# Acuator-MKI-RevisionCD.net
KiCad netlist of a schematic drawn in EAGLE
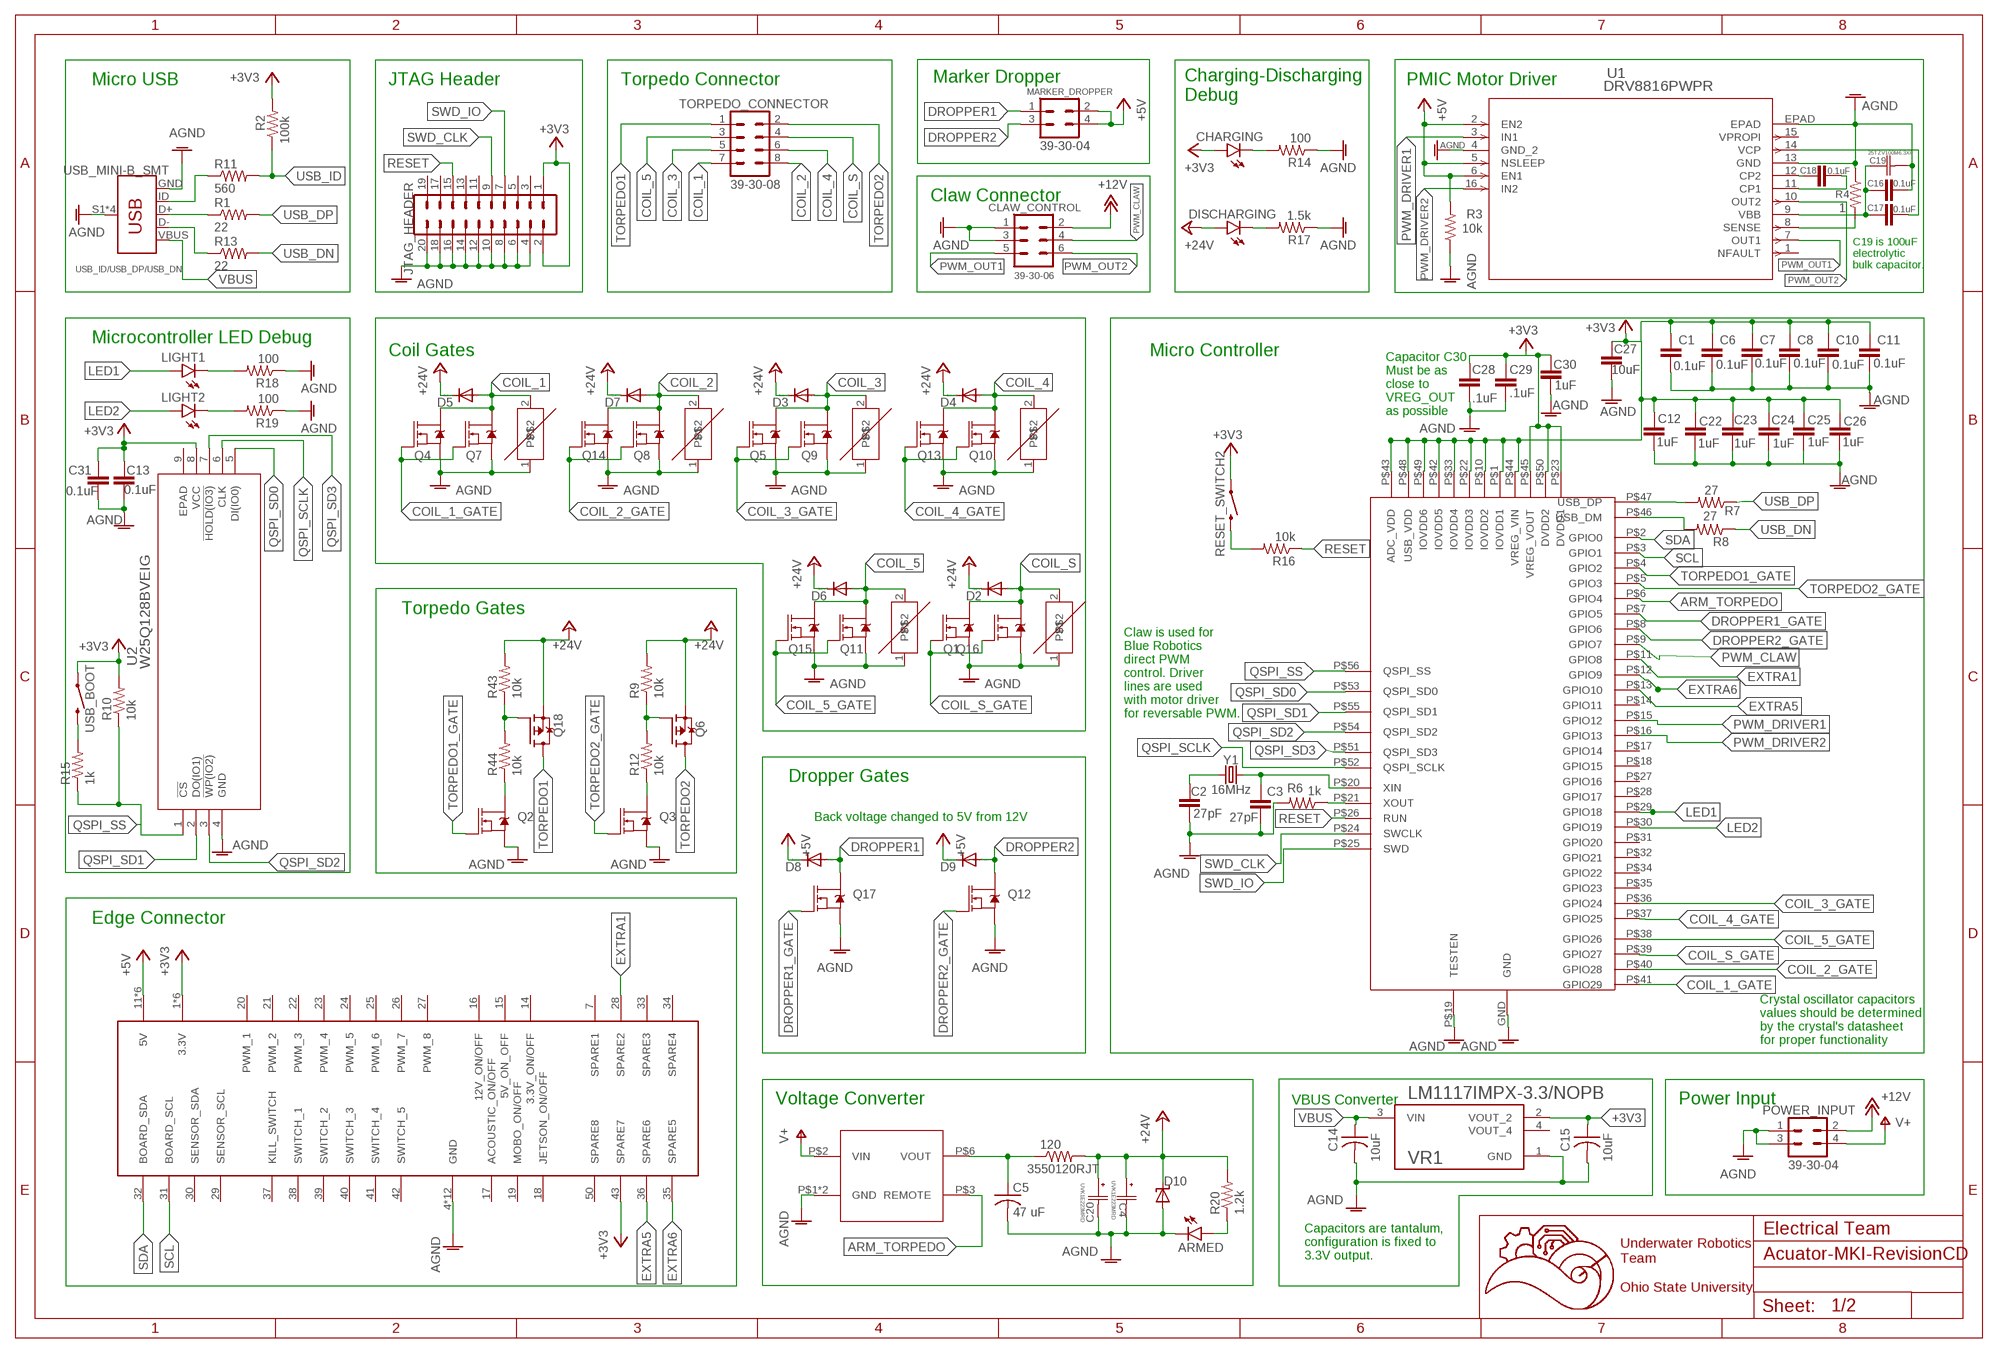
[diagram p0: schematic, sheet 1]
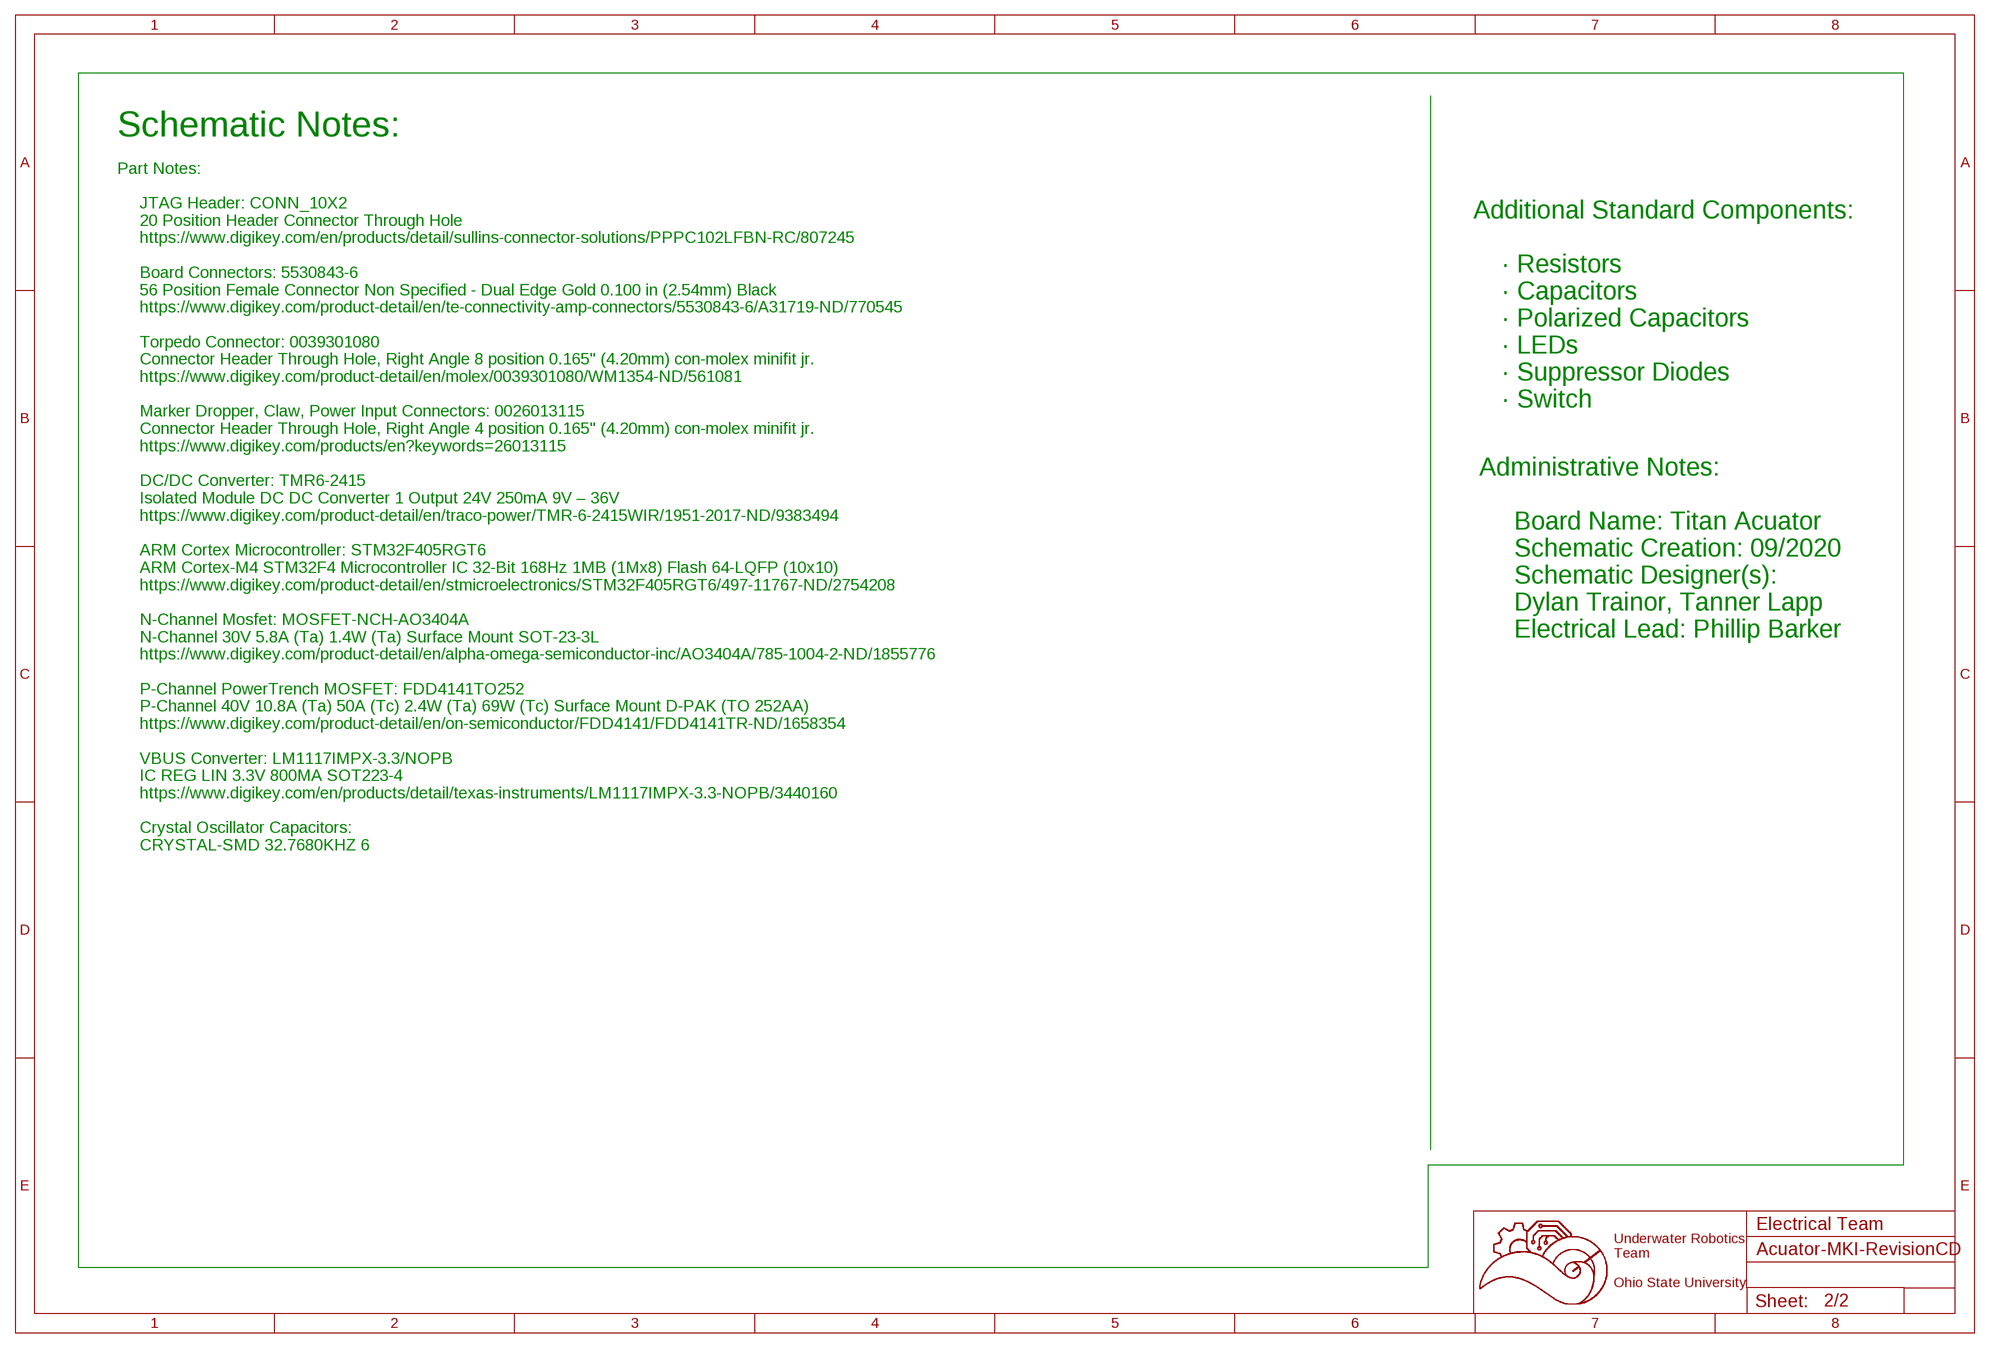
[diagram p1: schematic, sheet 2]

(export (version "E")
  (design (tool "Eeschema 10.0.6"))
  (components
    (comp (ref "120")
      (value "3550120RJT")
      (footprint "eagle-import:3550120RJT")
      (libsource (lib "eagle-import") (part "3550120RJT"))
    )
    (comp (ref "ARMED")
      (value "LEDCHIPLED_0603")
      (footprint "eagle-import:CHIPLED_0603")
      (libsource (lib "eagle-import") (part "LEDCHIPLED_0603"))
    )
    (comp (ref "C1")
      (value "0.1uF")
      (footprint "eagle-import:C0603")
      (libsource (lib "eagle-import") (part "C-EUC0603"))
    )
    (comp (ref "C2")
      (value "27pF")
      (footprint "eagle-import:C0603")
      (libsource (lib "eagle-import") (part "C-EUC0603"))
    )
    (comp (ref "C3")
      (value "27pF")
      (footprint "eagle-import:C0603")
      (libsource (lib "eagle-import") (part "C-EUC0603"))
    )
    (comp (ref "C4")
      (value "UVK1E223MRD")
      (footprint "eagle-import:CAP_UFW_25X50_NCH")
      (fields (field (name "COPYRIGHT") "Copyright (C) 2018 Accelerated Designs. All rights reserved"))
      (libsource (lib "eagle-import") (part "UVK1E223MRD"))
    )
    (comp (ref "C5")
      (value "47 uF")
      (footprint "eagle-import:C1206K")
      (libsource (lib "eagle-import") (part "resistor_348_C-USC1206K"))
    )
    (comp (ref "C6")
      (value "0.1uF")
      (footprint "eagle-import:C0603")
      (libsource (lib "eagle-import") (part "C-EUC0603"))
    )
    (comp (ref "C7")
      (value "0.1uF")
      (footprint "eagle-import:C0603")
      (libsource (lib "eagle-import") (part "C-EUC0603"))
    )
    (comp (ref "C8")
      (value "0.1uF")
      (footprint "eagle-import:C0603")
      (libsource (lib "eagle-import") (part "C-EUC0603"))
    )
    (comp (ref "C10")
      (value "0.1uF")
      (footprint "eagle-import:C0603")
      (libsource (lib "eagle-import") (part "C-EUC0603"))
    )
    (comp (ref "C11")
      (value "0.1uF")
      (footprint "eagle-import:C0603")
      (libsource (lib "eagle-import") (part "C-EUC0603"))
    )
    (comp (ref "C12")
      (value "1uF")
      (footprint "eagle-import:C0603")
      (libsource (lib "eagle-import") (part "C-EUC0603"))
    )
    (comp (ref "C13")
      (value "0.1uF")
      (footprint "eagle-import:C0603")
      (libsource (lib "eagle-import") (part "C-EUC0603"))
    )
    (comp (ref "C14")
      (value "10uF")
      (footprint "eagle-import:C0603")
      (libsource (lib "eagle-import") (part "C-USC0603"))
    )
    (comp (ref "C15")
      (value "10uF")
      (footprint "eagle-import:C0603")
      (libsource (lib "eagle-import") (part "C-USC0603"))
    )
    (comp (ref "C16")
      (value "0.1uF")
      (footprint "eagle-import:C0603")
      (libsource (lib "eagle-import") (part "C-EUC0603"))
    )
    (comp (ref "C17")
      (value "0.1uF")
      (footprint "eagle-import:C0603")
      (libsource (lib "eagle-import") (part "C-EUC0603"))
    )
    (comp (ref "C18")
      (value "0.1uF")
      (footprint "eagle-import:C0603")
      (libsource (lib "eagle-import") (part "C-EUC0603"))
    )
    (comp (ref "C19")
      (value "25TZV100M6.3X8")
      (footprint "eagle-import:CAP_J-V_6P3X8_RUB")
      (fields (field (name "COPYRIGHT") "Copyright (C) 2018 Accelerated Designs. All rights reserved"))
      (libsource (lib "eagle-import") (part "25TZV100M6.3X8"))
    )
    (comp (ref "C20")
      (value "UVK1E223MRD")
      (footprint "eagle-import:CAP_UFW_25X50_NCH")
      (fields (field (name "COPYRIGHT") "Copyright (C) 2018 Accelerated Designs. All rights reserved"))
      (libsource (lib "eagle-import") (part "UVK1E223MRD"))
    )
    (comp (ref "C22")
      (value "1uF")
      (footprint "eagle-import:C0603")
      (libsource (lib "eagle-import") (part "C-EUC0603"))
    )
    (comp (ref "C23")
      (value "1uF")
      (footprint "eagle-import:C0603")
      (libsource (lib "eagle-import") (part "C-EUC0603"))
    )
    (comp (ref "C24")
      (value "1uF")
      (footprint "eagle-import:C0603")
      (libsource (lib "eagle-import") (part "C-EUC0603"))
    )
    (comp (ref "C25")
      (value "1uF")
      (footprint "eagle-import:C0603")
      (libsource (lib "eagle-import") (part "C-EUC0603"))
    )
    (comp (ref "C26")
      (value "1uF")
      (footprint "eagle-import:C0603")
      (libsource (lib "eagle-import") (part "C-EUC0603"))
    )
    (comp (ref "C27")
      (value "10uF")
      (footprint "eagle-import:C0603")
      (libsource (lib "eagle-import") (part "C-EUC0603"))
    )
    (comp (ref "C28")
      (value ".1uF")
      (footprint "eagle-import:C0603")
      (libsource (lib "eagle-import") (part "C-EUC0603"))
    )
    (comp (ref "C29")
      (value ".1uF")
      (footprint "eagle-import:C0603")
      (libsource (lib "eagle-import") (part "C-EUC0603"))
    )
    (comp (ref "C30")
      (value "1uF")
      (footprint "eagle-import:C0603")
      (libsource (lib "eagle-import") (part "C-EUC0603"))
    )
    (comp (ref "C31")
      (value "0.1uF")
      (footprint "eagle-import:C0603")
      (libsource (lib "eagle-import") (part "C-EUC0603"))
    )
    (comp (ref "CHARGING")
      (value "LEDCHIPLED_0603")
      (footprint "eagle-import:CHIPLED_0603")
      (libsource (lib "eagle-import") (part "LEDCHIPLED_0603"))
    )
    (comp (ref "CLAW_CONTROL")
      (value "39-30-06")
      (footprint "eagle-import:39-30-_06_")
      (libsource (lib "eagle-import") (part "39-30-?06?"))
    )
    (comp (ref "D2")
      (value "DIODE-SMB")
      (footprint "eagle-import:SMB")
      (libsource (lib "eagle-import") (part "DIODE-SMB"))
    )
    (comp (ref "D3")
      (value "DIODE-SMB")
      (footprint "eagle-import:SMB")
      (libsource (lib "eagle-import") (part "DIODE-SMB"))
    )
    (comp (ref "D4")
      (value "DIODE-SMB")
      (footprint "eagle-import:SMB")
      (libsource (lib "eagle-import") (part "DIODE-SMB"))
    )
    (comp (ref "D5")
      (value "DIODE-SMB")
      (footprint "eagle-import:SMB")
      (libsource (lib "eagle-import") (part "DIODE-SMB"))
    )
    (comp (ref "D6")
      (value "DIODE-SMB")
      (footprint "eagle-import:SMB")
      (libsource (lib "eagle-import") (part "DIODE-SMB"))
    )
    (comp (ref "D7")
      (value "DIODE-SMB")
      (footprint "eagle-import:SMB")
      (libsource (lib "eagle-import") (part "DIODE-SMB"))
    )
    (comp (ref "D8")
      (value "DIODE-SMB")
      (footprint "eagle-import:SMB")
      (libsource (lib "eagle-import") (part "DIODE-SMB"))
    )
    (comp (ref "D9")
      (value "DIODE-SMB")
      (footprint "eagle-import:SMB")
      (libsource (lib "eagle-import") (part "DIODE-SMB"))
    )
    (comp (ref "D10")
      (value "SUPPRESSOR-SMBJ")
      (footprint "eagle-import:SMBJ")
      (libsource (lib "eagle-import") (part "SUPPRESSOR-SMBJ"))
    )
    (comp (ref "DISCHARGING")
      (value "LEDCHIPLED_0603")
      (footprint "eagle-import:CHIPLED_0603")
      (libsource (lib "eagle-import") (part "LEDCHIPLED_0603"))
    )
    (comp (ref "JTAG_HEADER")
      (value "CONN_10X2")
      (footprint "eagle-import:2X10")
      (libsource (lib "eagle-import") (part "CONN_10X2"))
    )
    (comp (ref "LIGHT1")
      (value "LEDCHIPLED_0603")
      (footprint "eagle-import:CHIPLED_0603")
      (libsource (lib "eagle-import") (part "LEDCHIPLED_0603"))
    )
    (comp (ref "LIGHT2")
      (value "LEDCHIPLED_0603")
      (footprint "eagle-import:CHIPLED_0603")
      (libsource (lib "eagle-import") (part "LEDCHIPLED_0603"))
    )
    (comp (ref "MARKER_DROPPER")
      (value "39-30-04")
      (footprint "eagle-import:39-30-_04_")
      (libsource (lib "eagle-import") (part "39-30-?04?"))
    )
    (comp (ref "POWER_INPUT")
      (value "39-30-04")
      (footprint "eagle-import:39-30-_04_")
      (libsource (lib "eagle-import") (part "39-30-?04?"))
    )
    (comp (ref "Q1")
      (value "MOSFET-NCH-AO3404A")
      (footprint "eagle-import:SOT23-3")
      (libsource (lib "eagle-import") (part "MOSFET-NCH-AO3404A"))
    )
    (comp (ref "Q2")
      (value "MOSFET-NCH-AO3404A")
      (footprint "eagle-import:SOT23-3")
      (libsource (lib "eagle-import") (part "MOSFET-NCH-AO3404A"))
    )
    (comp (ref "Q3")
      (value "MOSFET-NCH-AO3404A")
      (footprint "eagle-import:SOT23-3")
      (libsource (lib "eagle-import") (part "MOSFET-NCH-AO3404A"))
    )
    (comp (ref "Q4")
      (value "MOSFET-NCH-AO3404A")
      (footprint "eagle-import:SOT23-3")
      (libsource (lib "eagle-import") (part "MOSFET-NCH-AO3404A"))
    )
    (comp (ref "Q5")
      (value "MOSFET-NCH-AO3404A")
      (footprint "eagle-import:SOT23-3")
      (libsource (lib "eagle-import") (part "MOSFET-NCH-AO3404A"))
    )
    (comp (ref "Q6")
      (value "FDD4141TO252")
      (footprint "eagle-import:TO252")
      (libsource (lib "eagle-import") (part "FDD4141TO252"))
    )
    (comp (ref "Q7")
      (value "MOSFET-NCH-AO3404A")
      (footprint "eagle-import:SOT23-3")
      (libsource (lib "eagle-import") (part "MOSFET-NCH-AO3404A"))
    )
    (comp (ref "Q8")
      (value "MOSFET-NCH-AO3404A")
      (footprint "eagle-import:SOT23-3")
      (libsource (lib "eagle-import") (part "MOSFET-NCH-AO3404A"))
    )
    (comp (ref "Q9")
      (value "MOSFET-NCH-AO3404A")
      (footprint "eagle-import:SOT23-3")
      (libsource (lib "eagle-import") (part "MOSFET-NCH-AO3404A"))
    )
    (comp (ref "Q10")
      (value "MOSFET-NCH-AO3404A")
      (footprint "eagle-import:SOT23-3")
      (libsource (lib "eagle-import") (part "MOSFET-NCH-AO3404A"))
    )
    (comp (ref "Q11")
      (value "MOSFET-NCH-AO3404A")
      (footprint "eagle-import:SOT23-3")
      (libsource (lib "eagle-import") (part "MOSFET-NCH-AO3404A"))
    )
    (comp (ref "Q12")
      (value "MOSFET-NCH-AO3404A")
      (footprint "eagle-import:SOT23-3")
      (libsource (lib "eagle-import") (part "MOSFET-NCH-AO3404A"))
    )
    (comp (ref "Q13")
      (value "MOSFET-NCH-AO3404A")
      (footprint "eagle-import:SOT23-3")
      (libsource (lib "eagle-import") (part "MOSFET-NCH-AO3404A"))
    )
    (comp (ref "Q14")
      (value "MOSFET-NCH-AO3404A")
      (footprint "eagle-import:SOT23-3")
      (libsource (lib "eagle-import") (part "MOSFET-NCH-AO3404A"))
    )
    (comp (ref "Q15")
      (value "MOSFET-NCH-AO3404A")
      (footprint "eagle-import:SOT23-3")
      (libsource (lib "eagle-import") (part "MOSFET-NCH-AO3404A"))
    )
    (comp (ref "Q16")
      (value "MOSFET-NCH-AO3404A")
      (footprint "eagle-import:SOT23-3")
      (libsource (lib "eagle-import") (part "MOSFET-NCH-AO3404A"))
    )
    (comp (ref "Q17")
      (value "MOSFET-NCH-AO3404A")
      (footprint "eagle-import:SOT23-3")
      (libsource (lib "eagle-import") (part "MOSFET-NCH-AO3404A"))
    )
    (comp (ref "Q18")
      (value "FDD4141TO252")
      (footprint "eagle-import:TO252")
      (libsource (lib "eagle-import") (part "FDD4141TO252"))
    )
    (comp (ref "R1")
      (value "22")
      (footprint "eagle-import:R0603")
      (libsource (lib "eagle-import") (part "R-US_R0603"))
    )
    (comp (ref "R2")
      (value "100k")
      (footprint "eagle-import:R0603")
      (libsource (lib "eagle-import") (part "R-US_R0603"))
    )
    (comp (ref "R3")
      (value "10k")
      (footprint "eagle-import:R0603")
      (libsource (lib "eagle-import") (part "resistor_348_R-US_R0603"))
    )
    (comp (ref "R4")
      (value "1")
      (footprint "eagle-import:R0805")
      (libsource (lib "eagle-import") (part "resistor_348_R-US_R0805"))
    )
    (comp (ref "R6")
      (value "1k")
      (footprint "eagle-import:R0603")
      (libsource (lib "eagle-import") (part "R-US_R0603"))
    )
    (comp (ref "R7")
      (value "27")
      (footprint "eagle-import:R0603")
      (libsource (lib "eagle-import") (part "R-US_R0603"))
    )
    (comp (ref "R8")
      (value "27")
      (footprint "eagle-import:R0603")
      (libsource (lib "eagle-import") (part "R-US_R0603"))
    )
    (comp (ref "R9")
      (value "10k")
      (footprint "eagle-import:R0603")
      (libsource (lib "eagle-import") (part "resistor_348_R-US_R0603"))
    )
    (comp (ref "R10")
      (value "10k")
      (footprint "eagle-import:R0603")
      (libsource (lib "eagle-import") (part "R-US_R0603"))
    )
    (comp (ref "R11")
      (value "560")
      (footprint "eagle-import:R0603")
      (libsource (lib "eagle-import") (part "R-US_R0603"))
    )
    (comp (ref "R12")
      (value "10k")
      (footprint "eagle-import:R0603")
      (libsource (lib "eagle-import") (part "resistor_348_R-US_R0603"))
    )
    (comp (ref "R13")
      (value "22")
      (footprint "eagle-import:R0603")
      (libsource (lib "eagle-import") (part "R-US_R0603"))
    )
    (comp (ref "R14")
      (value "100")
      (footprint "eagle-import:R0805")
      (libsource (lib "eagle-import") (part "resistor_348_R-US_R0805"))
    )
    (comp (ref "R15")
      (value "1k")
      (footprint "eagle-import:R0603")
      (libsource (lib "eagle-import") (part "R-US_R0603"))
    )
    (comp (ref "R16")
      (value "10k")
      (footprint "eagle-import:R0603")
      (libsource (lib "eagle-import") (part "R-US_R0603"))
    )
    (comp (ref "R17")
      (value "1.5k")
      (footprint "eagle-import:R0805")
      (libsource (lib "eagle-import") (part "resistor_348_R-US_R0805"))
    )
    (comp (ref "R18")
      (value "100")
      (footprint "eagle-import:R0805")
      (libsource (lib "eagle-import") (part "resistor_348_R-US_R0805"))
    )
    (comp (ref "R19")
      (value "100")
      (footprint "eagle-import:R0805")
      (libsource (lib "eagle-import") (part "resistor_348_R-US_R0805"))
    )
    (comp (ref "R20")
      (value "1.2k")
      (footprint "eagle-import:R0805")
      (libsource (lib "eagle-import") (part "resistor_348_R-US_R0805"))
    )
    (comp (ref "R43")
      (value "10k")
      (footprint "eagle-import:R0603")
      (libsource (lib "eagle-import") (part "resistor_348_R-US_R0603"))
    )
    (comp (ref "R44")
      (value "10k")
      (footprint "eagle-import:R0603")
      (libsource (lib "eagle-import") (part "resistor_348_R-US_R0603"))
    )
    (comp (ref "RESET_SWITCH2")
      (value "MOMENTARY-SWITCH-SPST-PTH-6.0MM")
      (footprint "eagle-import:TACTILE_SWITCH_PTH_6.0MM")
      (libsource (lib "eagle-import") (part "MOMENTARY-SWITCH-SPST-PTH-6.0MM"))
    )
    (comp (ref "TORPEDO_CONNECTOR")
      (value "39-30-08")
      (footprint "eagle-import:39-30-_08_")
      (libsource (lib "eagle-import") (part "39-30-?08?"))
    )
    (comp (ref "U$1")
      (value "5530843-EDGE")
      (footprint "eagle-import:5530843-6-BOARDFINGERS")
      (libsource (lib "eagle-import") (part "5530843-EDGE"))
    )
    (comp (ref "U$2")
      (value "ERZ-VF2M270ERZ-VF2M270")
      (footprint "eagle-import:RESM8060X320N")
      (libsource (lib "eagle-import") (part "ERZ-VF2M270ERZ-VF2M270"))
    )
    (comp (ref "U$3")
      (value "ERZ-VF2M270ERZ-VF2M270")
      (footprint "eagle-import:RESM8060X320N")
      (libsource (lib "eagle-import") (part "ERZ-VF2M270ERZ-VF2M270"))
    )
    (comp (ref "U$4")
      (value "ERZ-VF2M270ERZ-VF2M270")
      (footprint "eagle-import:RESM8060X320N")
      (libsource (lib "eagle-import") (part "ERZ-VF2M270ERZ-VF2M270"))
    )
    (comp (ref "U$5")
      (value "ERZ-VF2M270ERZ-VF2M270")
      (footprint "eagle-import:RESM8060X320N")
      (libsource (lib "eagle-import") (part "ERZ-VF2M270ERZ-VF2M270"))
    )
    (comp (ref "U$6")
      (value "TMR6-2415")
      (footprint "eagle-import:TMR6-2415")
      (libsource (lib "eagle-import") (part "TMR6-2415"))
    )
    (comp (ref "U$7")
      (value "ERZ-VF2M270ERZ-VF2M270")
      (footprint "eagle-import:RESM8060X320N")
      (libsource (lib "eagle-import") (part "ERZ-VF2M270ERZ-VF2M270"))
    )
    (comp (ref "U$8")
      (value "ERZ-VF2M270ERZ-VF2M270")
      (footprint "eagle-import:RESM8060X320N")
      (libsource (lib "eagle-import") (part "ERZ-VF2M270ERZ-VF2M270"))
    )
    (comp (ref "U$9")
      (value "RP2040")
      (footprint "eagle-import:RP2040")
      (libsource (lib "eagle-import") (part "RP2040"))
    )
    (comp (ref "U1")
      (value "DRV8816PWPR")
      (footprint "eagle-import:PWP_16")
      (libsource (lib "eagle-import") (part "DRV8816PWPR"))
    )
    (comp (ref "U2")
      (value "W25Q128BVEIG")
      (footprint "eagle-import:WIN_E-8_WIN")
      (fields (field (name "COPYRIGHT") "Copyright (C) 2021 Ultra Librarian. All rights reserved."))
      (libsource (lib "eagle-import") (part "W25Q128BVEIG"))
    )
    (comp (ref "USB_BOOT")
      (value "MOMENTARY-SWITCH-SPST-PTH-6.0MM")
      (footprint "eagle-import:TACTILE_SWITCH_PTH_6.0MM")
      (libsource (lib "eagle-import") (part "MOMENTARY-SWITCH-SPST-PTH-6.0MM"))
    )
    (comp (ref "USB_ID/USB_DP/USB_DN")
      (value "USB_MINI-B_SMT")
      (footprint "eagle-import:USB-MINIB")
      (libsource (lib "eagle-import") (part "USB_MINI-B_SMT"))
    )
    (comp (ref "VR1")
      (value "LM1117IMPX-3.3/NOPB")
      (footprint "eagle-import:VREG_LM1117IMPX-3.3_NOPB")
      (fields (field (name "MF") "Texas Instruments"))
      (libsource (lib "eagle-import") (part "LM1117IMPX-3.3/NOPB"))
    )
    (comp (ref "Y1")
      (value "16MHz")
      (footprint "eagle-import:HC49US")
      (libsource (lib "eagle-import") (part "CRYSTAL-16MHZPTH-HC49US"))
    )
  )
  (nets
    (net (code "1") (name "+3V3") (class "Default")
      (node (ref "C1") (pin "1") (pinfunction "1_1") (pintype "passive"))
      (node (ref "C10") (pin "1") (pinfunction "1_1") (pintype "passive"))
      (node (ref "C11") (pin "1") (pinfunction "1_1") (pintype "passive"))
      (node (ref "C12") (pin "1") (pinfunction "1_1") (pintype "passive"))
      (node (ref "C13") (pin "1") (pinfunction "1_1") (pintype "passive"))
      (node (ref "C15") (pin "1") (pinfunction "1_1") (pintype "passive"))
      (node (ref "C22") (pin "1") (pinfunction "1_1") (pintype "passive"))
      (node (ref "C23") (pin "1") (pinfunction "1_1") (pintype "passive"))
      (node (ref "C24") (pin "1") (pinfunction "1_1") (pintype "passive"))
      (node (ref "C25") (pin "1") (pinfunction "1_1") (pintype "passive"))
      (node (ref "C26") (pin "1") (pinfunction "1_1") (pintype "passive"))
      (node (ref "C27") (pin "1") (pinfunction "1_1") (pintype "passive"))
      (node (ref "C28") (pin "1") (pinfunction "1_1") (pintype "passive"))
      (node (ref "C29") (pin "1") (pinfunction "1_1") (pintype "passive"))
      (node (ref "C30") (pin "1") (pinfunction "1_1") (pintype "passive"))
      (node (ref "C31") (pin "1") (pinfunction "1_1") (pintype "passive"))
      (node (ref "C6") (pin "1") (pinfunction "1_1") (pintype "passive"))
      (node (ref "C7") (pin "1") (pinfunction "1_1") (pintype "passive"))
      (node (ref "C8") (pin "1") (pinfunction "1_1") (pintype "passive"))
      (node (ref "CHARGING") (pin "A") (pinfunction "A_A") (pintype "passive"))
      (node (ref "JTAG_HEADER") (pin "1") (pinfunction "1_1") (pintype "passive"))
      (node (ref "JTAG_HEADER") (pin "2") (pinfunction "2_2") (pintype "passive"))
      (node (ref "R10") (pin "2") (pinfunction "2_2") (pintype "passive"))
      (node (ref "R2") (pin "2") (pinfunction "2_2") (pintype "passive"))
      (node (ref "RESET_SWITCH2") (pin "1") (pinfunction "1_1") (pintype "passive"))
      (node (ref "U$1") (pin "1") (pinfunction "3.3V_1") (pintype "bidirectional"))
      (node (ref "U$1") (pin "2") (pinfunction "3.3V_2") (pintype "bidirectional"))
      (node (ref "U$1") (pin "3") (pinfunction "3.3V_3") (pintype "bidirectional"))
      (node (ref "U$1") (pin "43") (pinfunction "SPARE7_43") (pintype "bidirectional"))
      (node (ref "U$1") (pin "54") (pinfunction "3.3V_54") (pintype "bidirectional"))
      (node (ref "U$1") (pin "55") (pinfunction "3.3V_55") (pintype "bidirectional"))
      (node (ref "U$1") (pin "56") (pinfunction "3.3V_56") (pintype "bidirectional"))
      (node (ref "U$9") (pin "P$1") (pinfunction "IOVDD1_P$1") (pintype "bidirectional"))
      (node (ref "U$9") (pin "P$10") (pinfunction "IOVDD2_P$10") (pintype "bidirectional"))
      (node (ref "U$9") (pin "P$22") (pinfunction "IOVDD3_P$22") (pintype "bidirectional"))
      (node (ref "U$9") (pin "P$23") (pinfunction "DVDD1_P$23") (pintype "bidirectional"))
      (node (ref "U$9") (pin "P$33") (pinfunction "IOVDD4_P$33") (pintype "bidirectional"))
      (node (ref "U$9") (pin "P$42") (pinfunction "IOVDD5_P$42") (pintype "bidirectional"))
      (node (ref "U$9") (pin "P$43") (pinfunction "ADC_VDD_P$43") (pintype "bidirectional"))
      (node (ref "U$9") (pin "P$44") (pinfunction "VREG_VIN_P$44") (pintype "bidirectional"))
      (node (ref "U$9") (pin "P$45") (pinfunction "VREG_VOUT_P$45") (pintype "bidirectional"))
      (node (ref "U$9") (pin "P$48") (pinfunction "USB_VDD_P$48") (pintype "bidirectional"))
      (node (ref "U$9") (pin "P$49") (pinfunction "IOVDD6_P$49") (pintype "bidirectional"))
      (node (ref "U$9") (pin "P$50") (pinfunction "DVDD2_P$50") (pintype "bidirectional"))
      (node (ref "U2") (pin "8") (pinfunction "VCC_8") (pintype "power_in"))
      (node (ref "USB_BOOT") (pin "1") (pinfunction "1_1") (pintype "passive"))
      (node (ref "VR1") (pin "2") (pinfunction "VOUT_2_2") (pintype "output"))
    )
    (net (code "2") (name "+5V") (class "Default")
      (node (ref "D8") (pin "C") (pinfunction "C_C") (pintype "passive"))
      (node (ref "D9") (pin "C") (pinfunction "C_C") (pintype "passive"))
      (node (ref "MARKER_DROPPER") (pin "2") (pinfunction "2_2") (pintype "passive"))
      (node (ref "MARKER_DROPPER") (pin "4") (pinfunction "4_4") (pintype "passive"))
      (node (ref "R3") (pin "2") (pinfunction "2_2") (pintype "passive"))
      (node (ref "U$1") (pin "11") (pinfunction "5V_11") (pintype "bidirectional"))
      (node (ref "U$1") (pin "12") (pinfunction "5V_12") (pintype "bidirectional"))
      (node (ref "U$1") (pin "13") (pinfunction "5V_13") (pintype "bidirectional"))
      (node (ref "U$1") (pin "44") (pinfunction "5V_44") (pintype "bidirectional"))
      (node (ref "U$1") (pin "45") (pinfunction "5V_45") (pintype "bidirectional"))
      (node (ref "U$1") (pin "46") (pinfunction "5V_46") (pintype "bidirectional"))
      (node (ref "U1") (pin "2") (pinfunction "EN2_2") (pintype "input"))
      (node (ref "U1") (pin "5") (pinfunction "NSLEEP_5") (pintype "input"))
      (node (ref "U1") (pin "6") (pinfunction "EN1_6") (pintype "input"))
    )
    (net (code "3") (name "+12V") (class "Default")
      (node (ref "CLAW_CONTROL") (pin "2") (pinfunction "2_2") (pintype "passive"))
      (node (ref "POWER_INPUT") (pin "2") (pinfunction "2_2") (pintype "passive"))
    )
    (net (code "4") (name "+24V") (class "Default")
      (node (ref "120") (pin "P$2") (pinfunction "2_P$2") (pintype "passive"))
      (node (ref "C20") (pin "1") (pinfunction "1_1") (pintype "passive"))
      (node (ref "C4") (pin "1") (pinfunction "1_1") (pintype "passive"))
      (node (ref "D10") (pin "C") (pinfunction "C_C") (pintype "passive"))
      (node (ref "D2") (pin "C") (pinfunction "C_C") (pintype "passive"))
      (node (ref "D3") (pin "C") (pinfunction "C_C") (pintype "passive"))
      (node (ref "D4") (pin "C") (pinfunction "C_C") (pintype "passive"))
      (node (ref "D5") (pin "C") (pinfunction "C_C") (pintype "passive"))
      (node (ref "D6") (pin "C") (pinfunction "C_C") (pintype "passive"))
      (node (ref "D7") (pin "C") (pinfunction "C_C") (pintype "passive"))
      (node (ref "DISCHARGING") (pin "A") (pinfunction "A_A") (pintype "passive"))
      (node (ref "Q18") (pin "2") (pinfunction "S_2") (pintype "passive"))
      (node (ref "Q6") (pin "2") (pinfunction "S_2") (pintype "passive"))
      (node (ref "R20") (pin "2") (pinfunction "2_2") (pintype "passive"))
      (node (ref "R43") (pin "2") (pinfunction "2_2") (pintype "passive"))
      (node (ref "R9") (pin "2") (pinfunction "2_2") (pintype "passive"))
    )
    (net (code "5") (name "AGND") (class "Default")
      (node (ref "ARMED") (pin "C") (pinfunction "C_C") (pintype "passive"))
      (node (ref "C1") (pin "2") (pinfunction "2_2") (pintype "passive"))
      (node (ref "C10") (pin "2") (pinfunction "2_2") (pintype "passive"))
      (node (ref "C11") (pin "2") (pinfunction "2_2") (pintype "passive"))
      (node (ref "C12") (pin "2") (pinfunction "2_2") (pintype "passive"))
      (node (ref "C13") (pin "2") (pinfunction "2_2") (pintype "passive"))
      (node (ref "C14") (pin "2") (pinfunction "2_2") (pintype "passive"))
      (node (ref "C15") (pin "2") (pinfunction "2_2") (pintype "passive"))
      (node (ref "C16") (pin "2") (pinfunction "2_2") (pintype "passive"))
      (node (ref "C19") (pin "2") (pinfunction "2_2") (pintype "passive"))
      (node (ref "C2") (pin "2") (pinfunction "2_2") (pintype "passive"))
      (node (ref "C20") (pin "2") (pinfunction "2_2") (pintype "passive"))
      (node (ref "C22") (pin "2") (pinfunction "2_2") (pintype "passive"))
      (node (ref "C23") (pin "2") (pinfunction "2_2") (pintype "passive"))
      (node (ref "C24") (pin "2") (pinfunction "2_2") (pintype "passive"))
      (node (ref "C25") (pin "2") (pinfunction "2_2") (pintype "passive"))
      (node (ref "C26") (pin "2") (pinfunction "2_2") (pintype "passive"))
      (node (ref "C27") (pin "2") (pinfunction "2_2") (pintype "passive"))
      (node (ref "C28") (pin "2") (pinfunction "2_2") (pintype "passive"))
      (node (ref "C29") (pin "2") (pinfunction "2_2") (pintype "passive"))
      (node (ref "C3") (pin "2") (pinfunction "2_2") (pintype "passive"))
      (node (ref "C30") (pin "2") (pinfunction "2_2") (pintype "passive"))
      (node (ref "C31") (pin "2") (pinfunction "2_2") (pintype "passive"))
      (node (ref "C4") (pin "2") (pinfunction "2_2") (pintype "passive"))
      (node (ref "C5") (pin "2") (pinfunction "2_2") (pintype "passive"))
      (node (ref "C6") (pin "2") (pinfunction "2_2") (pintype "passive"))
      (node (ref "C7") (pin "2") (pinfunction "2_2") (pintype "passive"))
      (node (ref "C8") (pin "2") (pinfunction "2_2") (pintype "passive"))
      (node (ref "CLAW_CONTROL") (pin "1") (pinfunction "1_1") (pintype "passive"))
      (node (ref "CLAW_CONTROL") (pin "3") (pinfunction "3_3") (pintype "passive"))
      (node (ref "D10") (pin "A") (pinfunction "A_A") (pintype "passive"))
      (node (ref "JTAG_HEADER") (pin "10") (pinfunction "10_10") (pintype "passive"))
      (node (ref "JTAG_HEADER") (pin "12") (pinfunction "12_12") (pintype "passive"))
      (node (ref "JTAG_HEADER") (pin "14") (pinfunction "14_14") (pintype "passive"))
      (node (ref "JTAG_HEADER") (pin "16") (pinfunction "16_16") (pintype "passive"))
      (node (ref "JTAG_HEADER") (pin "18") (pinfunction "18_18") (pintype "passive"))
      (node (ref "JTAG_HEADER") (pin "20") (pinfunction "20_20") (pintype "passive"))
      (node (ref "JTAG_HEADER") (pin "4") (pinfunction "4_4") (pintype "passive"))
      (node (ref "JTAG_HEADER") (pin "6") (pinfunction "6_6") (pintype "passive"))
      (node (ref "JTAG_HEADER") (pin "8") (pinfunction "8_8") (pintype "passive"))
      (node (ref "POWER_INPUT") (pin "1") (pinfunction "1_1") (pintype "passive"))
      (node (ref "POWER_INPUT") (pin "3") (pinfunction "3_3") (pintype "passive"))
      (node (ref "Q1") (pin "2") (pinfunction "S_2") (pintype "bidirectional"))
      (node (ref "Q10") (pin "2") (pinfunction "S_2") (pintype "bidirectional"))
      (node (ref "Q11") (pin "2") (pinfunction "S_2") (pintype "bidirectional"))
      (node (ref "Q12") (pin "2") (pinfunction "S_2") (pintype "bidirectional"))
      (node (ref "Q13") (pin "2") (pinfunction "S_2") (pintype "bidirectional"))
      (node (ref "Q14") (pin "2") (pinfunction "S_2") (pintype "bidirectional"))
      (node (ref "Q15") (pin "2") (pinfunction "S_2") (pintype "bidirectional"))
      (node (ref "Q16") (pin "2") (pinfunction "S_2") (pintype "bidirectional"))
      (node (ref "Q17") (pin "2") (pinfunction "S_2") (pintype "bidirectional"))
      (node (ref "Q2") (pin "2") (pinfunction "S_2") (pintype "bidirectional"))
      (node (ref "Q3") (pin "2") (pinfunction "S_2") (pintype "bidirectional"))
      (node (ref "Q4") (pin "2") (pinfunction "S_2") (pintype "bidirectional"))
      (node (ref "Q5") (pin "2") (pinfunction "S_2") (pintype "bidirectional"))
      (node (ref "Q7") (pin "2") (pinfunction "S_2") (pintype "bidirectional"))
      (node (ref "Q8") (pin "2") (pinfunction "S_2") (pintype "bidirectional"))
      (node (ref "Q9") (pin "2") (pinfunction "S_2") (pintype "bidirectional"))
      (node (ref "R14") (pin "1") (pinfunction "1_1") (pintype "passive"))
      (node (ref "R17") (pin "1") (pinfunction "1_1") (pintype "passive"))
      (node (ref "R18") (pin "1") (pinfunction "1_1") (pintype "passive"))
      (node (ref "R19") (pin "1") (pinfunction "1_1") (pintype "passive"))
      (node (ref "R3") (pin "1") (pinfunction "1_1") (pintype "passive"))
      (node (ref "R4") (pin "1") (pinfunction "1_1") (pintype "passive"))
      (node (ref "R6") (pin "2") (pinfunction "2_2") (pintype "passive"))
      (node (ref "U$1") (pin "10") (pinfunction "GND_10") (pintype "bidirectional"))
      (node (ref "U$1") (pin "4") (pinfunction "GND_4") (pintype "bidirectional"))
      (node (ref "U$1") (pin "47") (pinfunction "GND_47") (pintype "bidirectional"))
      (node (ref "U$1") (pin "48") (pinfunction "GND_48") (pintype "bidirectional"))
      (node (ref "U$1") (pin "49") (pinfunction "GND_49") (pintype "bidirectional"))
      (node (ref "U$1") (pin "5") (pinfunction "GND_5") (pintype "bidirectional"))
      (node (ref "U$1") (pin "51") (pinfunction "GND_51") (pintype "bidirectional"))
      (node (ref "U$1") (pin "52") (pinfunction "GND_52") (pintype "bidirectional"))
      (node (ref "U$1") (pin "53") (pinfunction "GND_53") (pintype "bidirectional"))
      (node (ref "U$1") (pin "6") (pinfunction "GND_6") (pintype "bidirectional"))
      (node (ref "U$1") (pin "8") (pinfunction "GND_8") (pintype "bidirectional"))
      (node (ref "U$1") (pin "9") (pinfunction "GND_9") (pintype "bidirectional"))
      (node (ref "U$2") (pin "1") (pinfunction "P$1_1") (pintype "bidirectional"))
      (node (ref "U$3") (pin "1") (pinfunction "P$1_1") (pintype "bidirectional"))
      (node (ref "U$4") (pin "1") (pinfunction "P$1_1") (pintype "bidirectional"))
      (node (ref "U$5") (pin "1") (pinfunction "P$1_1") (pintype "bidirectional"))
      (node (ref "U$6") (pin "P$1") (pinfunction "GND_P$1") (pintype "bidirectional"))
      (node (ref "U$6") (pin "P$7") (pinfunction "GND_P$7") (pintype "bidirectional"))
      (node (ref "U$7") (pin "1") (pinfunction "P$1_1") (pintype "bidirectional"))
      (node (ref "U$8") (pin "1") (pinfunction "P$1_1") (pintype "bidirectional"))
      (node (ref "U$9") (pin "GND") (pinfunction "GND_GND") (pintype "bidirectional"))
      (node (ref "U$9") (pin "P$19") (pinfunction "TESTEN_P$19") (pintype "bidirectional"))
      (node (ref "U1") (pin "13") (pinfunction "GND_13") (pintype "power_in"))
      (node (ref "U1") (pin "4") (pinfunction "GND_2_4") (pintype "power_in"))
      (node (ref "U1") (pin "EPAD") (pinfunction "EPAD_EPAD") (pintype "passive"))
      (node (ref "U2") (pin "4") (pinfunction "GND_4") (pintype "power_in"))
      (node (ref "USB_ID/USB_DP/USB_DN") (pin "GND") (pinfunction "GND_GND") (pintype "power_in"))
      (node (ref "USB_ID/USB_DP/USB_DN") (pin "S1") (pinfunction "SHIELD_S1") (pintype "bidirectional"))
      (node (ref "USB_ID/USB_DP/USB_DN") (pin "S2") (pinfunction "SHIELD_S2") (pintype "bidirectional"))
      (node (ref "USB_ID/USB_DP/USB_DN") (pin "S3") (pinfunction "SHIELD_S3") (pintype "bidirectional"))
      (node (ref "USB_ID/USB_DP/USB_DN") (pin "S4") (pinfunction "SHIELD_S4") (pintype "bidirectional"))
      (node (ref "VR1") (pin "1") (pinfunction "GND_1") (pintype "power_in"))
    )
    (net (code "6") (name "ARM_TORPEDO") (class "Default")
      (node (ref "U$6") (pin "P$3") (pinfunction "REMOTE_P$3") (pintype "bidirectional"))
      (node (ref "U$9") (pin "P$6") (pinfunction "GPIO4_P$6") (pintype "bidirectional"))
    )
    (net (code "7") (name "COIL_1") (class "Default")
      (node (ref "D5") (pin "A") (pinfunction "A_A") (pintype "passive"))
      (node (ref "Q4") (pin "3") (pinfunction "D_3") (pintype "bidirectional"))
      (node (ref "Q7") (pin "3") (pinfunction "D_3") (pintype "bidirectional"))
      (node (ref "TORPEDO_CONNECTOR") (pin "7") (pinfunction "7_7") (pintype "passive"))
      (node (ref "U$8") (pin "2") (pinfunction "P$2_2") (pintype "bidirectional"))
    )
    (net (code "8") (name "COIL_1_GATE") (class "Default")
      (node (ref "Q4") (pin "1") (pinfunction "G_1") (pintype "bidirectional"))
      (node (ref "Q7") (pin "1") (pinfunction "G_1") (pintype "bidirectional"))
      (node (ref "U$9") (pin "P$41") (pinfunction "GPIO29_P$41") (pintype "bidirectional"))
    )
    (net (code "9") (name "COIL_2") (class "Default")
      (node (ref "D7") (pin "A") (pinfunction "A_A") (pintype "passive"))
      (node (ref "Q14") (pin "3") (pinfunction "D_3") (pintype "bidirectional"))
      (node (ref "Q8") (pin "3") (pinfunction "D_3") (pintype "bidirectional"))
      (node (ref "TORPEDO_CONNECTOR") (pin "8") (pinfunction "8_8") (pintype "passive"))
      (node (ref "U$7") (pin "2") (pinfunction "P$2_2") (pintype "bidirectional"))
    )
    (net (code "10") (name "COIL_2_GATE") (class "Default")
      (node (ref "Q14") (pin "1") (pinfunction "G_1") (pintype "bidirectional"))
      (node (ref "Q8") (pin "1") (pinfunction "G_1") (pintype "bidirectional"))
      (node (ref "U$9") (pin "P$40") (pinfunction "GPIO28_P$40") (pintype "bidirectional"))
    )
    (net (code "11") (name "COIL_3") (class "Default")
      (node (ref "D3") (pin "A") (pinfunction "A_A") (pintype "passive"))
      (node (ref "Q5") (pin "3") (pinfunction "D_3") (pintype "bidirectional"))
      (node (ref "Q9") (pin "3") (pinfunction "D_3") (pintype "bidirectional"))
      (node (ref "TORPEDO_CONNECTOR") (pin "5") (pinfunction "5_5") (pintype "passive"))
      (node (ref "U$5") (pin "2") (pinfunction "P$2_2") (pintype "bidirectional"))
    )
    (net (code "12") (name "COIL_3_GATE") (class "Default")
      (node (ref "Q5") (pin "1") (pinfunction "G_1") (pintype "bidirectional"))
      (node (ref "Q9") (pin "1") (pinfunction "G_1") (pintype "bidirectional"))
      (node (ref "U$9") (pin "P$36") (pinfunction "GPIO24_P$36") (pintype "bidirectional"))
    )
    (net (code "13") (name "COIL_4") (class "Default")
      (node (ref "D4") (pin "A") (pinfunction "A_A") (pintype "passive"))
      (node (ref "Q10") (pin "3") (pinfunction "D_3") (pintype "bidirectional"))
      (node (ref "Q13") (pin "3") (pinfunction "D_3") (pintype "bidirectional"))
      (node (ref "TORPEDO_CONNECTOR") (pin "6") (pinfunction "6_6") (pintype "passive"))
      (node (ref "U$4") (pin "2") (pinfunction "P$2_2") (pintype "bidirectional"))
    )
    (net (code "14") (name "COIL_4_GATE") (class "Default")
      (node (ref "Q10") (pin "1") (pinfunction "G_1") (pintype "bidirectional"))
      (node (ref "Q13") (pin "1") (pinfunction "G_1") (pintype "bidirectional"))
      (node (ref "U$9") (pin "P$37") (pinfunction "GPIO25_P$37") (pintype "bidirectional"))
    )
    (net (code "15") (name "COIL_5") (class "Default")
      (node (ref "D6") (pin "A") (pinfunction "A_A") (pintype "passive"))
      (node (ref "Q11") (pin "3") (pinfunction "D_3") (pintype "bidirectional"))
      (node (ref "Q15") (pin "3") (pinfunction "D_3") (pintype "bidirectional"))
      (node (ref "TORPEDO_CONNECTOR") (pin "3") (pinfunction "3_3") (pintype "passive"))
      (node (ref "U$3") (pin "2") (pinfunction "P$2_2") (pintype "bidirectional"))
    )
    (net (code "16") (name "COIL_5_GATE") (class "Default")
      (node (ref "Q11") (pin "1") (pinfunction "G_1") (pintype "bidirectional"))
      (node (ref "Q15") (pin "1") (pinfunction "G_1") (pintype "bidirectional"))
      (node (ref "U$9") (pin "P$38") (pinfunction "GPIO26_P$38") (pintype "bidirectional"))
    )
    (net (code "17") (name "COIL_S") (class "Default")
      (node (ref "D2") (pin "A") (pinfunction "A_A") (pintype "passive"))
      (node (ref "Q1") (pin "3") (pinfunction "D_3") (pintype "bidirectional"))
      (node (ref "Q16") (pin "3") (pinfunction "D_3") (pintype "bidirectional"))
      (node (ref "TORPEDO_CONNECTOR") (pin "4") (pinfunction "4_4") (pintype "passive"))
      (node (ref "U$2") (pin "2") (pinfunction "P$2_2") (pintype "bidirectional"))
    )
    (net (code "18") (name "COIL_S_GATE") (class "Default")
      (node (ref "Q1") (pin "1") (pinfunction "G_1") (pintype "bidirectional"))
      (node (ref "Q16") (pin "1") (pinfunction "G_1") (pintype "bidirectional"))
      (node (ref "U$9") (pin "P$39") (pinfunction "GPIO27_P$39") (pintype "bidirectional"))
    )
    (net (code "19") (name "DROPPER1") (class "Default")
      (node (ref "D8") (pin "A") (pinfunction "A_A") (pintype "passive"))
      (node (ref "MARKER_DROPPER") (pin "1") (pinfunction "1_1") (pintype "passive"))
      (node (ref "Q17") (pin "3") (pinfunction "D_3") (pintype "bidirectional"))
    )
    (net (code "20") (name "DROPPER1_GATE") (class "Default")
      (node (ref "Q17") (pin "1") (pinfunction "G_1") (pintype "bidirectional"))
      (node (ref "U$9") (pin "P$7") (pinfunction "GPIO5_P$7") (pintype "bidirectional"))
    )
    (net (code "21") (name "DROPPER2") (class "Default")
      (node (ref "D9") (pin "A") (pinfunction "A_A") (pintype "passive"))
      (node (ref "MARKER_DROPPER") (pin "3") (pinfunction "3_3") (pintype "passive"))
      (node (ref "Q12") (pin "3") (pinfunction "D_3") (pintype "bidirectional"))
    )
    (net (code "22") (name "DROPPER2_GATE") (class "Default")
      (node (ref "Q12") (pin "1") (pinfunction "G_1") (pintype "bidirectional"))
      (node (ref "U$9") (pin "P$8") (pinfunction "GPIO6_P$8") (pintype "bidirectional"))
    )
    (net (code "23") (name "EXTRA1") (class "Default")
      (node (ref "U$1") (pin "28") (pinfunction "SPARE2_28") (pintype "bidirectional"))
      (node (ref "U$9") (pin "P$11") (pinfunction "GPIO8_P$11") (pintype "bidirectional"))
    )
    (net (code "24") (name "EXTRA5") (class "Default")
      (node (ref "U$1") (pin "36") (pinfunction "SPARE6_36") (pintype "bidirectional"))
      (node (ref "U$9") (pin "P$13") (pinfunction "GPIO10_P$13") (pintype "bidirectional"))
    )
    (net (code "25") (name "EXTRA6") (class "Default")
      (node (ref "U$1") (pin "35") (pinfunction "SPARE5_35") (pintype "bidirectional"))
      (node (ref "U$9") (pin "P$12") (pinfunction "GPIO9_P$12") (pintype "bidirectional"))
    )
    (net (code "26") (name "LED1") (class "Default")
      (node (ref "LIGHT1") (pin "A") (pinfunction "A_A") (pintype "passive"))
      (node (ref "U$9") (pin "P$29") (pinfunction "GPIO18_P$29") (pintype "bidirectional"))
    )
    (net (code "27") (name "LED2") (class "Default")
      (node (ref "LIGHT2") (pin "A") (pinfunction "A_A") (pintype "passive"))
      (node (ref "U$9") (pin "P$30") (pinfunction "GPIO19_P$30") (pintype "bidirectional"))
    )
    (net (code "28") (name "Net-(120-1)") (class "Default")
      (node (ref "120") (pin "P$1") (pinfunction "1_P$1") (pintype "passive"))
      (node (ref "C5") (pin "1") (pinfunction "1_1") (pintype "passive"))
      (node (ref "U$6") (pin "P$6") (pinfunction "VOUT_P$6") (pintype "bidirectional"))
    )
    (net (code "29") (name "Net-(ARMED-PadA)") (class "Default")
      (node (ref "ARMED") (pin "A") (pinfunction "A_A") (pintype "passive"))
      (node (ref "R20") (pin "1") (pinfunction "1_1") (pintype "passive"))
    )
    (net (code "30") (name "Net-(C2-Pad1)") (class "Default")
      (node (ref "C2") (pin "1") (pinfunction "1_1") (pintype "passive"))
      (node (ref "Y1") (pin "1") (pinfunction "1_1") (pintype "passive"))
    )
    (net (code "31") (name "Net-(CHARGING-PadC)") (class "Default")
      (node (ref "CHARGING") (pin "C") (pinfunction "C_C") (pintype "passive"))
      (node (ref "R14") (pin "2") (pinfunction "2_2") (pintype "passive"))
    )
    (net (code "32") (name "Net-(DISCHARGING-PadC)") (class "Default")
      (node (ref "DISCHARGING") (pin "C") (pinfunction "C_C") (pintype "passive"))
      (node (ref "R17") (pin "2") (pinfunction "2_2") (pintype "passive"))
    )
    (net (code "33") (name "Net-(LIGHT1-PadC)") (class "Default")
      (node (ref "LIGHT1") (pin "C") (pinfunction "C_C") (pintype "passive"))
      (node (ref "R18") (pin "2") (pinfunction "2_2") (pintype "passive"))
    )
    (net (code "34") (name "Net-(LIGHT2-PadC)") (class "Default")
      (node (ref "LIGHT2") (pin "C") (pinfunction "C_C") (pintype "passive"))
      (node (ref "R19") (pin "2") (pinfunction "2_2") (pintype "passive"))
    )
    (net (code "35") (name "Net-(Q2-D)") (class "Default")
      (node (ref "Q2") (pin "3") (pinfunction "D_3") (pintype "bidirectional"))
      (node (ref "R44") (pin "1") (pinfunction "1_1") (pintype "passive"))
    )
    (net (code "36") (name "Net-(Q3-D)") (class "Default")
      (node (ref "Q3") (pin "3") (pinfunction "D_3") (pintype "bidirectional"))
      (node (ref "R12") (pin "1") (pinfunction "1_1") (pintype "passive"))
    )
    (net (code "37") (name "Net-(Q6-G)") (class "Default")
      (node (ref "Q6") (pin "1") (pinfunction "G_1") (pintype "passive"))
      (node (ref "R12") (pin "2") (pinfunction "2_2") (pintype "passive"))
      (node (ref "R9") (pin "1") (pinfunction "1_1") (pintype "passive"))
    )
    (net (code "38") (name "Net-(Q18-G)") (class "Default")
      (node (ref "Q18") (pin "1") (pinfunction "G_1") (pintype "passive"))
      (node (ref "R43") (pin "1") (pinfunction "1_1") (pintype "passive"))
      (node (ref "R44") (pin "2") (pinfunction "2_2") (pintype "passive"))
    )
    (net (code "39") (name "Net-(R1-Pad1)") (class "Default")
      (node (ref "R1") (pin "1") (pinfunction "1_1") (pintype "passive"))
      (node (ref "USB_ID/USB_DP/USB_DN") (pin "D+") (pinfunction "D+_D+") (pintype "bidirectional"))
    )
    (net (code "40") (name "Net-(R11-Pad1)") (class "Default")
      (node (ref "R11") (pin "1") (pinfunction "1_1") (pintype "passive"))
      (node (ref "USB_ID/USB_DP/USB_DN") (pin "ID") (pinfunction "ID_ID") (pintype "bidirectional"))
    )
    (net (code "41") (name "Net-(R13-Pad1)") (class "Default")
      (node (ref "R13") (pin "1") (pinfunction "1_1") (pintype "passive"))
      (node (ref "USB_ID/USB_DP/USB_DN") (pin "D-") (pinfunction "D-_D-") (pintype "bidirectional"))
    )
    (net (code "42") (name "Net-(RESET_SWITCH2-2)") (class "Default")
      (node (ref "R16") (pin "2") (pinfunction "2_2") (pintype "passive"))
      (node (ref "RESET_SWITCH2") (pin "3") (pinfunction "2_3") (pintype "passive"))
    )
    (net (code "43") (name "Net-(U$9-USB_DM)") (class "Default")
      (node (ref "R8") (pin "2") (pinfunction "2_2") (pintype "passive"))
      (node (ref "U$9") (pin "P$46") (pinfunction "USB_DM_P$46") (pintype "bidirectional"))
    )
    (net (code "44") (name "Net-(U$9-USB_DP)") (class "Default")
      (node (ref "R7") (pin "2") (pinfunction "2_2") (pintype "passive"))
      (node (ref "U$9") (pin "P$47") (pinfunction "USB_DP_P$47") (pintype "bidirectional"))
    )
    (net (code "45") (name "Net-(U$9-XIN)") (class "Default")
      (node (ref "C3") (pin "1") (pinfunction "1_1") (pintype "passive"))
      (node (ref "U$9") (pin "P$20") (pinfunction "XIN_P$20") (pintype "bidirectional"))
      (node (ref "Y1") (pin "2") (pinfunction "2_2") (pintype "passive"))
    )
    (net (code "46") (name "Net-(U$9-XOUT)") (class "Default")
      (node (ref "R6") (pin "1") (pinfunction "1_1") (pintype "passive"))
      (node (ref "U$9") (pin "P$21") (pinfunction "XOUT_P$21") (pintype "bidirectional"))
    )
    (net (code "47") (name "Net-(U1-CP1)") (class "Default")
      (node (ref "C18") (pin "2") (pinfunction "2_2") (pintype "passive"))
      (node (ref "U1") (pin "11") (pinfunction "CP1_11") (pintype "passive"))
    )
    (net (code "48") (name "Net-(U1-CP2)") (class "Default")
      (node (ref "C18") (pin "1") (pinfunction "1_1") (pintype "passive"))
      (node (ref "U1") (pin "12") (pinfunction "CP2_12") (pintype "passive"))
    )
    (net (code "49") (name "Net-(U1-SENSE)") (class "Default")
      (node (ref "R4") (pin "2") (pinfunction "2_2") (pintype "passive"))
      (node (ref "U1") (pin "8") (pinfunction "SENSE_8") (pintype "output"))
    )
    (net (code "50") (name "Net-(U1-VBB)") (class "Default")
      (node (ref "C16") (pin "1") (pinfunction "1_1") (pintype "passive"))
      (node (ref "C17") (pin "1") (pinfunction "1_1") (pintype "passive"))
      (node (ref "C19") (pin "1") (pinfunction "1_1") (pintype "passive"))
      (node (ref "U1") (pin "9") (pinfunction "VBB_9") (pintype "power_in"))
    )
    (net (code "51") (name "Net-(U1-VCP)") (class "Default")
      (node (ref "C17") (pin "2") (pinfunction "2_2") (pintype "passive"))
      (node (ref "U1") (pin "14") (pinfunction "VCP_14") (pintype "output"))
    )
    (net (code "52") (name "Net-(USB_BOOT-2)") (class "Default")
      (node (ref "R15") (pin "2") (pinfunction "2_2") (pintype "passive"))
      (node (ref "USB_BOOT") (pin "3") (pinfunction "2_3") (pintype "passive"))
    )
    (net (code "53") (name "PWM_CLAW") (class "Default")
      (node (ref "CLAW_CONTROL") (pin "4") (pinfunction "4_4") (pintype "passive"))
      (node (ref "U$9") (pin "P$9") (pinfunction "GPIO7_P$9") (pintype "bidirectional"))
    )
    (net (code "54") (name "PWM_DRIVER1") (class "Default")
      (node (ref "U$9") (pin "P$15") (pinfunction "GPIO12_P$15") (pintype "bidirectional"))
      (node (ref "U1") (pin "3") (pinfunction "IN1_3") (pintype "input"))
    )
    (net (code "55") (name "PWM_DRIVER2") (class "Default")
      (node (ref "U$9") (pin "P$16") (pinfunction "GPIO13_P$16") (pintype "bidirectional"))
      (node (ref "U1") (pin "16") (pinfunction "IN2_16") (pintype "input"))
    )
    (net (code "56") (name "PWM_OUT1") (class "Default")
      (node (ref "CLAW_CONTROL") (pin "5") (pinfunction "5_5") (pintype "passive"))
      (node (ref "U1") (pin "7") (pinfunction "OUT1_7") (pintype "output"))
    )
    (net (code "57") (name "PWM_OUT2") (class "Default")
      (node (ref "CLAW_CONTROL") (pin "6") (pinfunction "6_6") (pintype "passive"))
      (node (ref "U1") (pin "10") (pinfunction "OUT2_10") (pintype "output"))
    )
    (net (code "58") (name "QSPI_SCLK") (class "Default")
      (node (ref "U$9") (pin "P$52") (pinfunction "QSPI_SCLK_P$52") (pintype "bidirectional"))
      (node (ref "U2") (pin "6") (pinfunction "CLK_6") (pintype "input"))
    )
    (net (code "59") (name "QSPI_SD0") (class "Default")
      (node (ref "U$9") (pin "P$53") (pinfunction "QSPI_SD0_P$53") (pintype "bidirectional"))
      (node (ref "U2") (pin "5") (pinfunction "DI(IO0)_5") (pintype "bidirectional"))
    )
    (net (code "60") (name "QSPI_SD1") (class "Default")
      (node (ref "U$9") (pin "P$55") (pinfunction "QSPI_SD1_P$55") (pintype "bidirectional"))
      (node (ref "U2") (pin "2") (pinfunction "DO(IO1)_2") (pintype "bidirectional"))
    )
    (net (code "61") (name "QSPI_SD2") (class "Default")
      (node (ref "U$9") (pin "P$54") (pinfunction "QSPI_SD2_P$54") (pintype "bidirectional"))
      (node (ref "U2") (pin "3") (pinfunction "~{WP(IO2})_3") (pintype "bidirectional"))
    )
    (net (code "62") (name "QSPI_SD3") (class "Default")
      (node (ref "U$9") (pin "P$51") (pinfunction "QSPI_SD3_P$51") (pintype "bidirectional"))
      (node (ref "U2") (pin "7") (pinfunction "~{HOLD(IO3})_7") (pintype "bidirectional"))
    )
    (net (code "63") (name "QSPI_SS") (class "Default")
      (node (ref "R10") (pin "1") (pinfunction "1_1") (pintype "passive"))
      (node (ref "R15") (pin "1") (pinfunction "1_1") (pintype "passive"))
      (node (ref "U$9") (pin "P$56") (pinfunction "QSPI_SS_P$56") (pintype "bidirectional"))
      (node (ref "U2") (pin "1") (pinfunction "~{CS}_1") (pintype "input"))
    )
    (net (code "64") (name "RESET") (class "Default")
      (node (ref "JTAG_HEADER") (pin "15") (pinfunction "15_15") (pintype "passive"))
      (node (ref "R16") (pin "1") (pinfunction "1_1") (pintype "passive"))
      (node (ref "U$9") (pin "P$26") (pinfunction "RUN_P$26") (pintype "bidirectional"))
    )
    (net (code "65") (name "SCL") (class "Default")
      (node (ref "U$1") (pin "31") (pinfunction "BOARD_SCL_31") (pintype "bidirectional"))
      (node (ref "U$9") (pin "P$3") (pinfunction "GPIO1_P$3") (pintype "bidirectional"))
    )
    (net (code "66") (name "SDA") (class "Default")
      (node (ref "U$1") (pin "32") (pinfunction "BOARD_SDA_32") (pintype "bidirectional"))
      (node (ref "U$9") (pin "P$2") (pinfunction "GPIO0_P$2") (pintype "bidirectional"))
    )
    (net (code "67") (name "SWD_CLK") (class "Default")
      (node (ref "JTAG_HEADER") (pin "9") (pinfunction "9_9") (pintype "passive"))
      (node (ref "U$9") (pin "P$24") (pinfunction "SWCLK_P$24") (pintype "bidirectional"))
    )
    (net (code "68") (name "SWD_IO") (class "Default")
      (node (ref "JTAG_HEADER") (pin "7") (pinfunction "7_7") (pintype "passive"))
      (node (ref "U$9") (pin "P$25") (pinfunction "SWD_P$25") (pintype "bidirectional"))
    )
    (net (code "69") (name "TORPEDO1") (class "Default")
      (node (ref "Q18") (pin "3") (pinfunction "D_3") (pintype "passive"))
      (node (ref "TORPEDO_CONNECTOR") (pin "1") (pinfunction "1_1") (pintype "passive"))
    )
    (net (code "70") (name "TORPEDO1_GATE") (class "Default")
      (node (ref "Q2") (pin "1") (pinfunction "G_1") (pintype "bidirectional"))
      (node (ref "U$9") (pin "P$4") (pinfunction "GPIO2_P$4") (pintype "bidirectional"))
    )
    (net (code "71") (name "TORPEDO2") (class "Default")
      (node (ref "Q6") (pin "3") (pinfunction "D_3") (pintype "passive"))
      (node (ref "TORPEDO_CONNECTOR") (pin "2") (pinfunction "2_2") (pintype "passive"))
    )
    (net (code "72") (name "TORPEDO2_GATE") (class "Default")
      (node (ref "Q3") (pin "1") (pinfunction "G_1") (pintype "bidirectional"))
      (node (ref "U$9") (pin "P$5") (pinfunction "GPIO3_P$5") (pintype "bidirectional"))
    )
    (net (code "73") (name "USB_DN") (class "Default")
      (node (ref "R13") (pin "2") (pinfunction "2_2") (pintype "passive"))
      (node (ref "R8") (pin "1") (pinfunction "1_1") (pintype "passive"))
    )
    (net (code "74") (name "USB_DP") (class "Default")
      (node (ref "R1") (pin "2") (pinfunction "2_2") (pintype "passive"))
      (node (ref "R7") (pin "1") (pinfunction "1_1") (pintype "passive"))
    )
    (net (code "75") (name "USB_ID") (class "Default")
      (node (ref "R11") (pin "2") (pinfunction "2_2") (pintype "passive"))
      (node (ref "R2") (pin "1") (pinfunction "1_1") (pintype "passive"))
    )
    (net (code "76") (name "V+") (class "Default")
      (node (ref "POWER_INPUT") (pin "4") (pinfunction "4_4") (pintype "passive"))
      (node (ref "U$6") (pin "P$2") (pinfunction "VIN_P$2") (pintype "bidirectional"))
    )
    (net (code "77") (name "VBUS") (class "Default")
      (node (ref "C14") (pin "1") (pinfunction "1_1") (pintype "passive"))
      (node (ref "USB_ID/USB_DP/USB_DN") (pin "VBUS") (pinfunction "VBUS_VBUS") (pintype "power_in"))
      (node (ref "VR1") (pin "3") (pinfunction "VIN_3") (pintype "input"))
    )
    (net (code "78") (name "unconnected-(JTAG_HEADER-Pad3)") (class "Default")
      (node (ref "JTAG_HEADER") (pin "3") (pinfunction "3_3") (pintype "passive"))
    )
    (net (code "79") (name "unconnected-(JTAG_HEADER-Pad5)") (class "Default")
      (node (ref "JTAG_HEADER") (pin "5") (pinfunction "5_5") (pintype "passive"))
    )
    (net (code "80") (name "unconnected-(JTAG_HEADER-Pad11)") (class "Default")
      (node (ref "JTAG_HEADER") (pin "11") (pinfunction "11_11") (pintype "passive"))
    )
    (net (code "81") (name "unconnected-(JTAG_HEADER-Pad13)") (class "Default")
      (node (ref "JTAG_HEADER") (pin "13") (pinfunction "13_13") (pintype "passive"))
    )
    (net (code "82") (name "unconnected-(JTAG_HEADER-Pad17)") (class "Default")
      (node (ref "JTAG_HEADER") (pin "17") (pinfunction "17_17") (pintype "passive"))
    )
    (net (code "83") (name "unconnected-(JTAG_HEADER-Pad19)") (class "Default")
      (node (ref "JTAG_HEADER") (pin "19") (pinfunction "19_19") (pintype "passive"))
    )
    (net (code "84") (name "unconnected-(U$1-3.3V_ON{slash}OFF-Pad14)") (class "Default")
      (node (ref "U$1") (pin "14") (pinfunction "3.3V_ON/OFF_14") (pintype "bidirectional"))
    )
    (net (code "85") (name "unconnected-(U$1-5V_ON_OFF-Pad15)") (class "Default")
      (node (ref "U$1") (pin "15") (pinfunction "5V_ON_OFF_15") (pintype "bidirectional"))
    )
    (net (code "86") (name "unconnected-(U$1-12V_ON{slash}OFF-Pad16)") (class "Default")
      (node (ref "U$1") (pin "16") (pinfunction "12V_ON/OFF_16") (pintype "bidirectional"))
    )
    (net (code "87") (name "unconnected-(U$1-ACOUSTIC_ON{slash}OFF-Pad17)") (class "Default")
      (node (ref "U$1") (pin "17") (pinfunction "ACOUSTIC_ON/OFF_17") (pintype "bidirectional"))
    )
    (net (code "88") (name "unconnected-(U$1-JETSON_ON{slash}OFF-Pad18)") (class "Default")
      (node (ref "U$1") (pin "18") (pinfunction "JETSON_ON/OFF_18") (pintype "bidirectional"))
    )
    (net (code "89") (name "unconnected-(U$1-KILL_SWITCH-Pad37)") (class "Default")
      (node (ref "U$1") (pin "37") (pinfunction "KILL_SWITCH_37") (pintype "output"))
    )
    (net (code "90") (name "unconnected-(U$1-MOBO_ON{slash}OFF-Pad19)") (class "Default")
      (node (ref "U$1") (pin "19") (pinfunction "MOBO_ON/OFF_19") (pintype "bidirectional"))
    )
    (net (code "91") (name "unconnected-(U$1-PWM_1-Pad20)") (class "Default")
      (node (ref "U$1") (pin "20") (pinfunction "PWM_1_20") (pintype "bidirectional"))
    )
    (net (code "92") (name "unconnected-(U$1-PWM_2-Pad21)") (class "Default")
      (node (ref "U$1") (pin "21") (pinfunction "PWM_2_21") (pintype "bidirectional"))
    )
    (net (code "93") (name "unconnected-(U$1-PWM_3-Pad22)") (class "Default")
      (node (ref "U$1") (pin "22") (pinfunction "PWM_3_22") (pintype "bidirectional"))
    )
    (net (code "94") (name "unconnected-(U$1-PWM_4-Pad23)") (class "Default")
      (node (ref "U$1") (pin "23") (pinfunction "PWM_4_23") (pintype "bidirectional"))
    )
    (net (code "95") (name "unconnected-(U$1-PWM_5-Pad24)") (class "Default")
      (node (ref "U$1") (pin "24") (pinfunction "PWM_5_24") (pintype "bidirectional"))
    )
    (net (code "96") (name "unconnected-(U$1-PWM_6-Pad25)") (class "Default")
      (node (ref "U$1") (pin "25") (pinfunction "PWM_6_25") (pintype "bidirectional"))
    )
    (net (code "97") (name "unconnected-(U$1-PWM_7-Pad26)") (class "Default")
      (node (ref "U$1") (pin "26") (pinfunction "PWM_7_26") (pintype "bidirectional"))
    )
    (net (code "98") (name "unconnected-(U$1-PWM_8-Pad27)") (class "Default")
      (node (ref "U$1") (pin "27") (pinfunction "PWM_8_27") (pintype "bidirectional"))
    )
    (net (code "99") (name "unconnected-(U$1-SENSOR_SCL-Pad29)") (class "Default")
      (node (ref "U$1") (pin "29") (pinfunction "SENSOR_SCL_29") (pintype "bidirectional"))
    )
    (net (code "100") (name "unconnected-(U$1-SENSOR_SDA-Pad30)") (class "Default")
      (node (ref "U$1") (pin "30") (pinfunction "SENSOR_SDA_30") (pintype "bidirectional"))
    )
    (net (code "101") (name "unconnected-(U$1-SPARE1-Pad7)") (class "Default")
      (node (ref "U$1") (pin "7") (pinfunction "SPARE1_7") (pintype "bidirectional"))
    )
    (net (code "102") (name "unconnected-(U$1-SPARE3-Pad33)") (class "Default")
      (node (ref "U$1") (pin "33") (pinfunction "SPARE3_33") (pintype "bidirectional"))
    )
    (net (code "103") (name "unconnected-(U$1-SPARE4-Pad34)") (class "Default")
      (node (ref "U$1") (pin "34") (pinfunction "SPARE4_34") (pintype "bidirectional"))
    )
    (net (code "104") (name "unconnected-(U$1-SPARE8-Pad50)") (class "Default")
      (node (ref "U$1") (pin "50") (pinfunction "SPARE8_50") (pintype "bidirectional"))
    )
    (net (code "105") (name "unconnected-(U$1-SWITCH_1-Pad38)") (class "Default")
      (node (ref "U$1") (pin "38") (pinfunction "SWITCH_1_38") (pintype "output"))
    )
    (net (code "106") (name "unconnected-(U$1-SWITCH_2-Pad39)") (class "Default")
      (node (ref "U$1") (pin "39") (pinfunction "SWITCH_2_39") (pintype "output"))
    )
    (net (code "107") (name "unconnected-(U$1-SWITCH_3-Pad40)") (class "Default")
      (node (ref "U$1") (pin "40") (pinfunction "SWITCH_3_40") (pintype "output"))
    )
    (net (code "108") (name "unconnected-(U$1-SWITCH_4-Pad41)") (class "Default")
      (node (ref "U$1") (pin "41") (pinfunction "SWITCH_4_41") (pintype "output"))
    )
    (net (code "109") (name "unconnected-(U$1-SWITCH_5-Pad42)") (class "Default")
      (node (ref "U$1") (pin "42") (pinfunction "SWITCH_5_42") (pintype "output"))
    )
    (net (code "110") (name "unconnected-(U$9-GPIO11-PadP$14)") (class "Default")
      (node (ref "U$9") (pin "P$14") (pinfunction "GPIO11_P$14") (pintype "bidirectional"))
    )
    (net (code "111") (name "unconnected-(U$9-GPIO14-PadP$17)") (class "Default")
      (node (ref "U$9") (pin "P$17") (pinfunction "GPIO14_P$17") (pintype "bidirectional"))
    )
    (net (code "112") (name "unconnected-(U$9-GPIO15-PadP$18)") (class "Default")
      (node (ref "U$9") (pin "P$18") (pinfunction "GPIO15_P$18") (pintype "bidirectional"))
    )
    (net (code "113") (name "unconnected-(U$9-GPIO16-PadP$27)") (class "Default")
      (node (ref "U$9") (pin "P$27") (pinfunction "GPIO16_P$27") (pintype "bidirectional"))
    )
    (net (code "114") (name "unconnected-(U$9-GPIO17-PadP$28)") (class "Default")
      (node (ref "U$9") (pin "P$28") (pinfunction "GPIO17_P$28") (pintype "bidirectional"))
    )
    (net (code "115") (name "unconnected-(U$9-GPIO20-PadP$31)") (class "Default")
      (node (ref "U$9") (pin "P$31") (pinfunction "GPIO20_P$31") (pintype "bidirectional"))
    )
    (net (code "116") (name "unconnected-(U$9-GPIO21-PadP$32)") (class "Default")
      (node (ref "U$9") (pin "P$32") (pinfunction "GPIO21_P$32") (pintype "bidirectional"))
    )
    (net (code "117") (name "unconnected-(U$9-GPIO22-PadP$34)") (class "Default")
      (node (ref "U$9") (pin "P$34") (pinfunction "GPIO22_P$34") (pintype "bidirectional"))
    )
    (net (code "118") (name "unconnected-(U$9-GPIO23-PadP$35)") (class "Default")
      (node (ref "U$9") (pin "P$35") (pinfunction "GPIO23_P$35") (pintype "bidirectional"))
    )
    (net (code "119") (name "unconnected-(U1-NFAULT-Pad1)") (class "Default")
      (node (ref "U1") (pin "1") (pinfunction "NFAULT_1") (pintype "output"))
    )
    (net (code "120") (name "unconnected-(U1-VPROPI-Pad15)") (class "Default")
      (node (ref "U1") (pin "15") (pinfunction "VPROPI_15") (pintype "output"))
    )
    (net (code "121") (name "unconnected-(U2-EPAD-Pad9)") (class "Default")
      (node (ref "U2") (pin "9") (pinfunction "EPAD_9") (pintype "passive"))
    )
    (net (code "122") (name "unconnected-(VR1-VOUT_4-Pad4)") (class "Default")
      (node (ref "VR1") (pin "4") (pinfunction "VOUT_4_4") (pintype "output"))
    )
  )
)
